# hx711_uno_scheme.net
KiCad netlist of a schematic drawn in Altium Designer
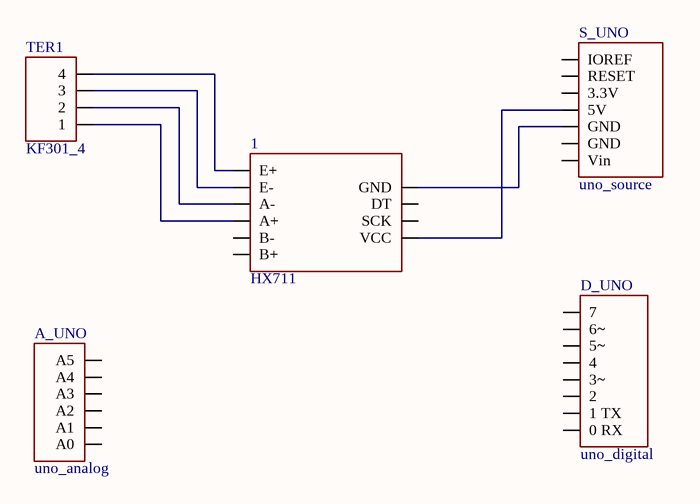
[diagram p0: hx711_uno_scheme.SchDoc]

(export (version "E")
  (design (tool "Eeschema 10.0.6"))
  (components
    (comp (ref "1")
      (value "HX711")
      (footprint "HX711")
      (libsource (lib "pcf_hx711_uno_shield") (part "HX711"))
    )
    (comp (ref "A_UNO")
      (value "uno_analog")
      (footprint "uno_analog")
      (libsource (lib "pcf_hx711_uno_shield") (part "uno_analog"))
    )
    (comp (ref "D_UNO")
      (value "uno_digital")
      (footprint "uno_digital")
      (libsource (lib "pcf_hx711_uno_shield") (part "uno_digital"))
    )
    (comp (ref "S_UNO")
      (value "uno_source")
      (footprint "uno_source")
      (libsource (lib "pcf_hx711_uno_shield") (part "uno_source"))
    )
    (comp (ref "TER1")
      (value "KF301_4")
      (footprint "KF304_place:KF304_4")
      (libsource (lib "pcf_hx711_uno_shield") (part "KF301_4"))
    )
  )
  (nets
    (net (code "1") (name "Net-(1-A+)") (class "Default")
      (node (ref "1") (pin "4") (pinfunction "A+_4") (pintype "passive"))
      (node (ref "TER1") (pin "1") (pinfunction "1_1") (pintype "passive"))
    )
    (net (code "2") (name "Net-(1-A-)") (class "Default")
      (node (ref "1") (pin "3") (pinfunction "A-_3") (pintype "passive"))
      (node (ref "TER1") (pin "2") (pinfunction "2_2") (pintype "passive"))
    )
    (net (code "3") (name "Net-(1-E+)") (class "Default")
      (node (ref "1") (pin "1") (pinfunction "E+_1") (pintype "passive"))
      (node (ref "TER1") (pin "4") (pinfunction "4_4") (pintype "passive"))
    )
    (net (code "4") (name "Net-(1-E-)") (class "Default")
      (node (ref "1") (pin "2") (pinfunction "E-_2") (pintype "passive"))
      (node (ref "TER1") (pin "3") (pinfunction "3_3") (pintype "passive"))
    )
    (net (code "5") (name "Net-(1-GND)") (class "Default")
      (node (ref "1") (pin "7") (pinfunction "GND_7") (pintype "passive"))
      (node (ref "S_UNO") (pin "2") (pinfunction "GND_2") (pintype "passive"))
    )
    (net (code "6") (name "Net-(1-VCC)") (class "Default")
      (node (ref "1") (pin "10") (pinfunction "VCC_10") (pintype "passive"))
      (node (ref "S_UNO") (pin "3") (pinfunction "5V_3") (pintype "passive"))
    )
    (net (code "7") (name "unconnected-(1-B+-Pad6)") (class "Default")
      (node (ref "1") (pin "6") (pinfunction "B+_6") (pintype "passive"))
    )
    (net (code "8") (name "unconnected-(1-B--Pad5)") (class "Default")
      (node (ref "1") (pin "5") (pinfunction "B-_5") (pintype "passive"))
    )
    (net (code "9") (name "unconnected-(1-DT-Pad8)") (class "Default")
      (node (ref "1") (pin "8") (pinfunction "DT_8") (pintype "passive"))
    )
    (net (code "10") (name "unconnected-(1-SCK-Pad9)") (class "Default")
      (node (ref "1") (pin "9") (pinfunction "SCK_9") (pintype "passive"))
    )
    (net (code "11") (name "unconnected-(A_UNO-A0-Pad0)") (class "Default")
      (node (ref "A_UNO") (pin "0") (pinfunction "A0_0") (pintype "passive"))
    )
    (net (code "12") (name "unconnected-(A_UNO-A1-Pad1)") (class "Default")
      (node (ref "A_UNO") (pin "1") (pinfunction "A1_1") (pintype "passive"))
    )
    (net (code "13") (name "unconnected-(A_UNO-A2-Pad2)") (class "Default")
      (node (ref "A_UNO") (pin "2") (pinfunction "A2_2") (pintype "passive"))
    )
    (net (code "14") (name "unconnected-(A_UNO-A3-Pad3)") (class "Default")
      (node (ref "A_UNO") (pin "3") (pinfunction "A3_3") (pintype "passive"))
    )
    (net (code "15") (name "unconnected-(A_UNO-A4-Pad4)") (class "Default")
      (node (ref "A_UNO") (pin "4") (pinfunction "A4_4") (pintype "passive"))
    )
    (net (code "16") (name "unconnected-(A_UNO-A5-Pad5)") (class "Default")
      (node (ref "A_UNO") (pin "5") (pinfunction "A5_5") (pintype "passive"))
    )
    (net (code "17") (name "unconnected-(D_UNO-0_RX-Pad0)") (class "Default")
      (node (ref "D_UNO") (pin "0") (pinfunction "0_RX_0") (pintype "passive"))
    )
    (net (code "18") (name "unconnected-(D_UNO-1_TX-Pad1)") (class "Default")
      (node (ref "D_UNO") (pin "1") (pinfunction "1_TX_1") (pintype "passive"))
    )
    (net (code "19") (name "unconnected-(D_UNO-3~-Pad3)") (class "Default")
      (node (ref "D_UNO") (pin "3") (pinfunction "3~_3") (pintype "passive"))
    )
    (net (code "20") (name "unconnected-(D_UNO-5~-Pad)") (class "Default")
      (node (ref "D_UNO") (pin "") (pinfunction "5~_") (pintype "passive"))
    )
    (net (code "21") (name "unconnected-(D_UNO-6~-Pad6)") (class "Default")
      (node (ref "D_UNO") (pin "6") (pinfunction "6~_6") (pintype "passive"))
    )
    (net (code "22") (name "unconnected-(D_UNO-Pad2)") (class "Default")
      (node (ref "D_UNO") (pin "2") (pinfunction "2_2") (pintype "passive"))
    )
    (net (code "23") (name "unconnected-(D_UNO-Pad4)") (class "Default")
      (node (ref "D_UNO") (pin "4") (pinfunction "4_4") (pintype "passive"))
    )
    (net (code "24") (name "unconnected-(D_UNO-Pad7)") (class "Default")
      (node (ref "D_UNO") (pin "7") (pinfunction "7_7") (pintype "passive"))
    )
    (net (code "25") (name "unconnected-(S_UNO-3.3V-Pad4)") (class "Default")
      (node (ref "S_UNO") (pin "4") (pinfunction "3.3V_4") (pintype "passive"))
    )
    (net (code "26") (name "unconnected-(S_UNO-GND-Pad1)") (class "Default")
      (node (ref "S_UNO") (pin "1") (pinfunction "GND_1") (pintype "passive"))
    )
    (net (code "27") (name "unconnected-(S_UNO-IOREF-Pad6)") (class "Default")
      (node (ref "S_UNO") (pin "6") (pinfunction "IOREF_6") (pintype "passive"))
    )
    (net (code "28") (name "unconnected-(S_UNO-RESET-Pad5)") (class "Default")
      (node (ref "S_UNO") (pin "5") (pinfunction "RESET_5") (pintype "passive"))
    )
    (net (code "29") (name "unconnected-(S_UNO-Vin-Pad0)") (class "Default")
      (node (ref "S_UNO") (pin "0") (pinfunction "Vin_0") (pintype "passive"))
    )
  )
)
